# A4950_driver.net
KiCad netlist of a schematic drawn in Altium Designer
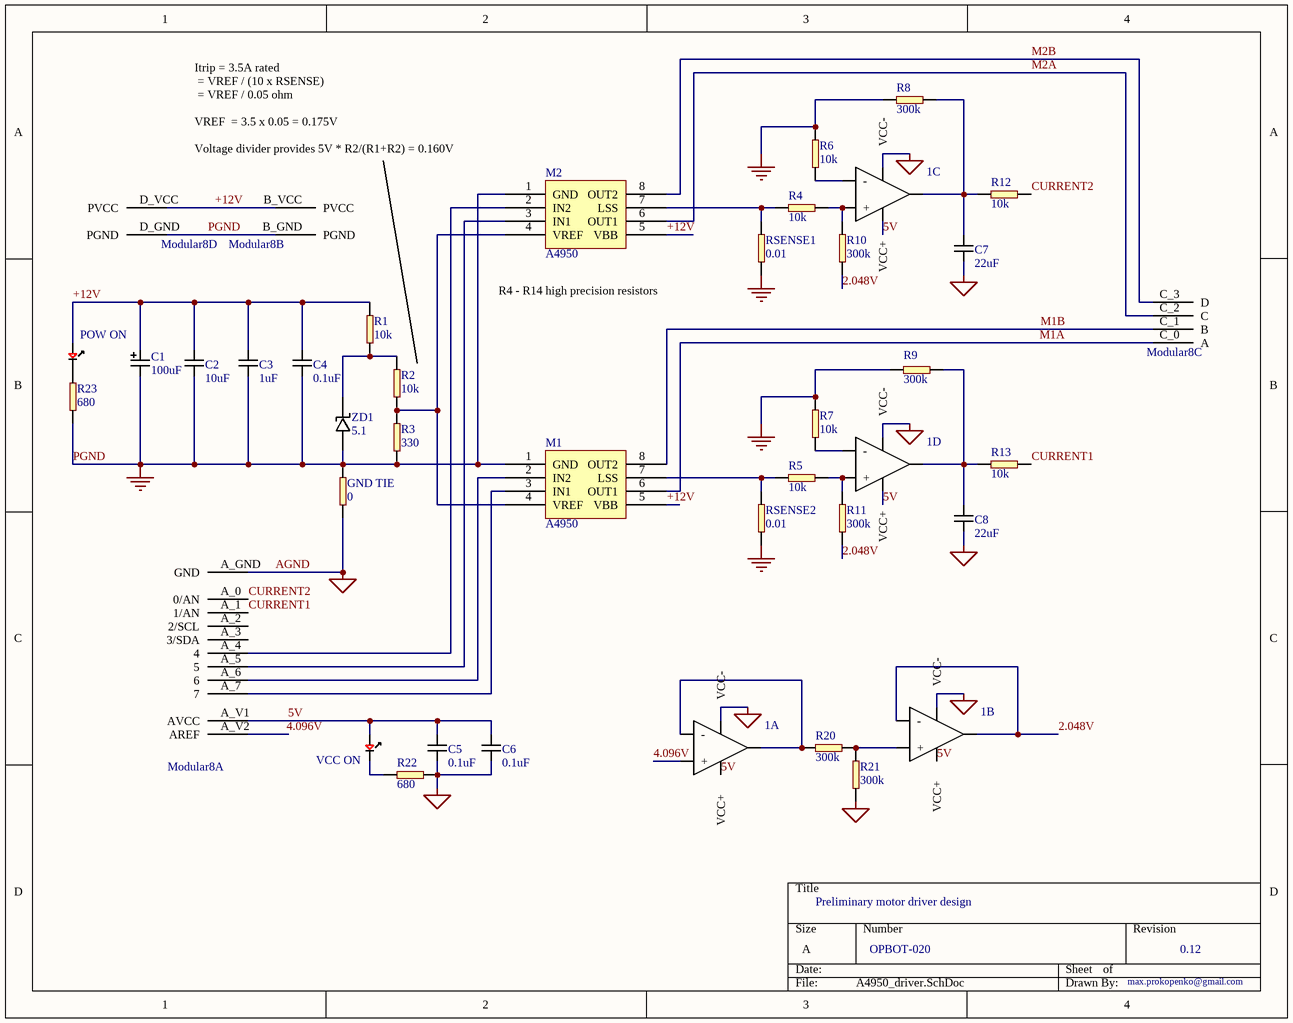
[diagram p0: A4950_driver.SchDoc]

(export (version "E")
  (design (tool "Eeschema 10.0.6"))
  (components
    (comp (ref "1") (value "LM324DT") (footprint "SO14") (libsource (lib "OpBots") (part "LM324DT")))
    (comp (ref "C1")
      (value "C 100uF 25V")
      (footprint "RADIAL CAP 6.5mm")
      (fields (field (name "C") "100uF"))
      (libsource (lib "RLC") (part "C 100uF 25V"))
    )
    (comp (ref "C2")
      (value "C 10uF 25V")
      (footprint "0603")
      (fields (field (name "C") "10uF"))
      (libsource (lib "RLC") (part "C 10uF 25V"))
    )
    (comp (ref "C3")
      (value "C 1uF 25V")
      (footprint "0603")
      (fields (field (name "C") "1uF"))
      (libsource (lib "RLC") (part "C 1uF 25V"))
    )
    (comp (ref "C4")
      (value "C 0.1uF 25V")
      (footprint "0603")
      (fields (field (name "C") "0.1uF"))
      (libsource (lib "RLC") (part "C 0.1uF 25V"))
    )
    (comp (ref "C5")
      (value "C 0.1uF 25V")
      (footprint "0603")
      (fields (field (name "C") "0.1uF"))
      (libsource (lib "RLC") (part "C 0.1uF 25V"))
    )
    (comp (ref "C6")
      (value "C 0.1uF 25V")
      (footprint "0603")
      (fields (field (name "C") "0.1uF"))
      (libsource (lib "RLC") (part "C 0.1uF 25V"))
    )
    (comp (ref "C7")
      (value "C 22uF 6.3V")
      (footprint "0603")
      (fields (field (name "C") "22uF"))
      (libsource (lib "RLC") (part "C 22uF 6.3V"))
    )
    (comp (ref "C8")
      (value "C 22uF 6.3V")
      (footprint "0603")
      (fields (field (name "C") "22uF"))
      (libsource (lib "RLC") (part "C 22uF 6.3V"))
    )
    (comp (ref "GND TIE")
      (value "R 0")
      (footprint "0603")
      (fields (field (name "R") "0"))
      (libsource (lib "RLC") (part "R 0"))
    )
    (comp (ref "M1")
      (value "A4950")
      (footprint "SOICN8 thermal pad")
      (libsource (lib "OpBots") (part "A4950"))
    )
    (comp (ref "M2")
      (value "A4950")
      (footprint "SOICN8 thermal pad")
      (libsource (lib "OpBots") (part "A4950"))
    )
    (comp (ref "Modular8")
      (value "modular8_power")
      (footprint "modular8 metric power")
      (libsource (lib "OpBots") (part "modular8_power"))
    )
    (comp (ref "POW ON") (value "LEDG") (footprint "0805 - LED") (libsource (lib "OpBots") (part "LEDG")))
    (comp (ref "R1")
      (value "R 10k")
      (footprint "0603")
      (fields (field (name "R") "10k"))
      (libsource (lib "RLC") (part "R 10k"))
    )
    (comp (ref "R2")
      (value "R 10k")
      (footprint "0603")
      (fields (field (name "R") "10k"))
      (libsource (lib "RLC") (part "R 10k"))
    )
    (comp (ref "R3")
      (value "R 330")
      (footprint "0603")
      (fields (field (name "R") "330"))
      (libsource (lib "RLC") (part "R 330"))
    )
    (comp (ref "R4")
      (value "R 10k 1%")
      (footprint "0603")
      (fields (field (name "R") "10k"))
      (libsource (lib "") (part "R 10k 1%_1"))
    )
    (comp (ref "R5")
      (value "R 10k 1%")
      (footprint "0603")
      (fields (field (name "R") "10k"))
      (libsource (lib "") (part "R 10k 1%_1"))
    )
    (comp (ref "R6")
      (value "R 10k 1%")
      (footprint "0603")
      (fields (field (name "R") "10k"))
      (libsource (lib "RLC") (part "R 10k 1%"))
    )
    (comp (ref "R7")
      (value "R 10k 1%")
      (footprint "0603")
      (fields (field (name "R") "10k"))
      (libsource (lib "RLC") (part "R 10k 1%"))
    )
    (comp (ref "R8")
      (value "R 300k 1%")
      (footprint "0603")
      (fields (field (name "R") "300k"))
      (libsource (lib "") (part "R 300k 1%_2"))
    )
    (comp (ref "R9")
      (value "R 300k 1%")
      (footprint "0603")
      (fields (field (name "R") "300k"))
      (libsource (lib "") (part "R 300k 1%_2"))
    )
    (comp (ref "R10")
      (value "R 300k 1%")
      (footprint "0603")
      (fields (field (name "R") "300k"))
      (libsource (lib "") (part "R 300k 1%_1"))
    )
    (comp (ref "R11")
      (value "R 300k 1%")
      (footprint "0603")
      (fields (field (name "R") "300k"))
      (libsource (lib "") (part "R 300k 1%_1"))
    )
    (comp (ref "R12")
      (value "R 10k")
      (footprint "0603")
      (fields (field (name "R") "10k"))
      (libsource (lib "") (part "R 10k_1"))
    )
    (comp (ref "R13")
      (value "R 10k")
      (footprint "0603")
      (fields (field (name "R") "10k"))
      (libsource (lib "") (part "R 10k_1"))
    )
    (comp (ref "R20")
      (value "R 300k 1%")
      (footprint "0603")
      (fields (field (name "R") "300k"))
      (libsource (lib "RLC") (part "R 300k 1%"))
    )
    (comp (ref "R21")
      (value "R 300k 1%")
      (footprint "0603")
      (fields (field (name "R") "300k"))
      (libsource (lib "") (part "R 300k 1%_1"))
    )
    (comp (ref "R22")
      (value "R 680")
      (footprint "0603")
      (fields (field (name "R") "680"))
      (libsource (lib "RLC") (part "R 680"))
    )
    (comp (ref "R23")
      (value "R 680")
      (footprint "0603")
      (fields (field (name "R") "680"))
      (libsource (lib "") (part "R 680_1"))
    )
    (comp (ref "RSENSE1")
      (value "R 0.01 0.5%")
      (footprint "1206 SPLIT")
      (fields (field (name "R") "0.01"))
      (libsource (lib "RLC") (part "R 0.01 0.5%"))
    )
    (comp (ref "RSENSE2")
      (value "R 0.01 0.5%")
      (footprint "1206 SPLIT")
      (fields (field (name "R") "0.01"))
      (libsource (lib "RLC") (part "R 0.01 0.5%"))
    )
    (comp (ref "VCC ON") (value "LEDG") (footprint "0805 - LED") (libsource (lib "OpBots") (part "LEDG")))
    (comp (ref "ZD1")
      (value "Zener 5.1V")
      (footprint "SOD-323F")
      (fields (field (name "VOLTAGE") "5.1"))
      (libsource (lib "OpBots") (part "Zener 5.1V"))
    )
  )
  (nets
    (net (code "1") (name "/+12V") (class "Default")
      (node (ref "C1") (pin "1") (pintype "passive"))
      (node (ref "C2") (pin "1") (pintype "passive"))
      (node (ref "C3") (pin "1") (pintype "passive"))
      (node (ref "C4") (pin "1") (pintype "passive"))
      (node (ref "M1") (pin "5") (pinfunction "VBB_5") (pintype "passive"))
      (node (ref "M2") (pin "5") (pinfunction "VBB_5") (pintype "passive"))
      (node (ref "Modular8") (pin "B_VCC") (pinfunction "PVCC_B_VCC") (pintype "passive"))
      (node (ref "Modular8") (pin "D_VCC") (pinfunction "PVCC_D_VCC") (pintype "passive"))
      (node (ref "POW ON") (pin "1") (pinfunction "A_1") (pintype "passive"))
      (node (ref "R1") (pin "1") (pintype "passive"))
    )
    (net (code "2") (name "/2.048V") (class "Default")
      (node (ref "1") (pin "6") (pinfunction "-_6") (pintype "passive"))
      (node (ref "1") (pin "7") (pinfunction "OUT_7") (pintype "passive"))
      (node (ref "R10") (pin "2") (pintype "passive"))
      (node (ref "R11") (pin "2") (pintype "passive"))
    )
    (net (code "3") (name "/4.096V") (class "Default")
      (node (ref "1") (pin "3") (pinfunction "+_3") (pintype "passive"))
      (node (ref "Modular8") (pin "A_V2") (pinfunction "AREF_A_V2") (pintype "passive"))
    )
    (net (code "4") (name "/5V") (class "Default")
      (node (ref "1") (pin "4") (pinfunction "VCC+_4") (pintype "passive"))
      (node (ref "C5") (pin "1") (pintype "passive"))
      (node (ref "C6") (pin "1") (pintype "passive"))
      (node (ref "Modular8") (pin "A_V1") (pinfunction "AVCC_A_V1") (pintype "passive"))
      (node (ref "VCC ON") (pin "1") (pinfunction "A_1") (pintype "passive"))
    )
    (net (code "5") (name "/CURRENT1") (class "Default")
      (node (ref "Modular8") (pin "A_1") (pinfunction "1/AN_A_1") (pintype "passive"))
      (node (ref "R13") (pin "2") (pintype "passive"))
    )
    (net (code "6") (name "/CURRENT2") (class "Default")
      (node (ref "Modular8") (pin "A_0") (pinfunction "0/AN_A_0") (pintype "passive"))
      (node (ref "R12") (pin "2") (pintype "passive"))
    )
    (net (code "7") (name "/M1A") (class "Default")
      (node (ref "M1") (pin "6") (pinfunction "OUT1_6") (pintype "passive"))
      (node (ref "Modular8") (pin "C_0") (pinfunction "A_C_0") (pintype "passive"))
    )
    (net (code "8") (name "/M1B") (class "Default")
      (node (ref "M1") (pin "8") (pinfunction "OUT2_8") (pintype "passive"))
      (node (ref "Modular8") (pin "C_1") (pinfunction "B_C_1") (pintype "passive"))
    )
    (net (code "9") (name "/M2A") (class "Default")
      (node (ref "M2") (pin "6") (pinfunction "OUT1_6") (pintype "passive"))
      (node (ref "Modular8") (pin "C_2") (pinfunction "C_C_2") (pintype "passive"))
    )
    (net (code "10") (name "/M2B") (class "Default")
      (node (ref "M2") (pin "8") (pinfunction "OUT2_8") (pintype "passive"))
      (node (ref "Modular8") (pin "C_3") (pinfunction "D_C_3") (pintype "passive"))
    )
    (net (code "11") (name "AGND") (class "Default")
      (node (ref "1") (pin "11") (pinfunction "VCC-_11") (pintype "passive"))
      (node (ref "C5") (pin "2") (pintype "passive"))
      (node (ref "C6") (pin "2") (pintype "passive"))
      (node (ref "C7") (pin "2") (pintype "passive"))
      (node (ref "C8") (pin "2") (pintype "passive"))
      (node (ref "GND TIE") (pin "2") (pintype "passive"))
      (node (ref "Modular8") (pin "A_GND") (pinfunction "GND_A_GND") (pintype "passive"))
      (node (ref "R21") (pin "2") (pintype "passive"))
      (node (ref "R22") (pin "2") (pintype "passive"))
    )
    (net (code "12") (name "Net-(1A--)") (class "Default")
      (node (ref "1") (pin "1") (pinfunction "OUT_1") (pintype "passive"))
      (node (ref "1") (pin "2") (pinfunction "-_2") (pintype "passive"))
      (node (ref "R20") (pin "2") (pintype "passive"))
    )
    (net (code "13") (name "Net-(1B-+)") (class "Default")
      (node (ref "1") (pin "5") (pinfunction "+_5") (pintype "passive"))
      (node (ref "R20") (pin "1") (pintype "passive"))
      (node (ref "R21") (pin "1") (pintype "passive"))
    )
    (net (code "14") (name "Net-(1C-+)") (class "Default")
      (node (ref "1") (pin "10") (pinfunction "+_10") (pintype "passive"))
      (node (ref "R10") (pin "1") (pintype "passive"))
      (node (ref "R4") (pin "2") (pintype "passive"))
    )
    (net (code "15") (name "Net-(1C--)") (class "Default")
      (node (ref "1") (pin "9") (pinfunction "-_9") (pintype "passive"))
      (node (ref "R6") (pin "1") (pintype "passive"))
    )
    (net (code "16") (name "Net-(1C-OUT)") (class "Default")
      (node (ref "1") (pin "8") (pinfunction "OUT_8") (pintype "passive"))
      (node (ref "C7") (pin "1") (pintype "passive"))
      (node (ref "R12") (pin "1") (pintype "passive"))
      (node (ref "R8") (pin "2") (pintype "passive"))
    )
    (net (code "17") (name "Net-(1D-+)") (class "Default")
      (node (ref "1") (pin "12") (pinfunction "+_12") (pintype "passive"))
      (node (ref "R11") (pin "1") (pintype "passive"))
      (node (ref "R5") (pin "2") (pintype "passive"))
    )
    (net (code "18") (name "Net-(1D--)") (class "Default")
      (node (ref "1") (pin "13") (pinfunction "-_13") (pintype "passive"))
      (node (ref "R7") (pin "1") (pintype "passive"))
    )
    (net (code "19") (name "Net-(1D-OUT)") (class "Default")
      (node (ref "1") (pin "14") (pinfunction "OUT_14") (pintype "passive"))
      (node (ref "C8") (pin "1") (pintype "passive"))
      (node (ref "R13") (pin "1") (pintype "passive"))
      (node (ref "R9") (pin "2") (pintype "passive"))
    )
    (net (code "20") (name "Net-(M1-IN1)") (class "Default")
      (node (ref "M1") (pin "3") (pinfunction "IN1_3") (pintype "passive"))
      (node (ref "Modular8") (pin "A_7") (pinfunction "7_A_7") (pintype "passive"))
    )
    (net (code "21") (name "Net-(M1-IN2)") (class "Default")
      (node (ref "M1") (pin "2") (pinfunction "IN2_2") (pintype "passive"))
      (node (ref "Modular8") (pin "A_6") (pinfunction "6_A_6") (pintype "passive"))
    )
    (net (code "22") (name "Net-(M1-LSS)") (class "Default")
      (node (ref "M1") (pin "7") (pinfunction "LSS_7") (pintype "passive"))
      (node (ref "R5") (pin "1") (pintype "passive"))
      (node (ref "RSENSE2") (pin "1") (pintype "passive"))
    )
    (net (code "23") (name "Net-(M1-VREF)") (class "Default")
      (node (ref "M1") (pin "4") (pinfunction "VREF_4") (pintype "passive"))
      (node (ref "M2") (pin "4") (pinfunction "VREF_4") (pintype "passive"))
      (node (ref "R2") (pin "2") (pintype "passive"))
      (node (ref "R3") (pin "1") (pintype "passive"))
    )
    (net (code "24") (name "Net-(M2-IN1)") (class "Default")
      (node (ref "M2") (pin "3") (pinfunction "IN1_3") (pintype "passive"))
      (node (ref "Modular8") (pin "A_5") (pinfunction "5_A_5") (pintype "passive"))
    )
    (net (code "25") (name "Net-(M2-IN2)") (class "Default")
      (node (ref "M2") (pin "2") (pinfunction "IN2_2") (pintype "passive"))
      (node (ref "Modular8") (pin "A_4") (pinfunction "4_A_4") (pintype "passive"))
    )
    (net (code "26") (name "Net-(M2-LSS)") (class "Default")
      (node (ref "M2") (pin "7") (pinfunction "LSS_7") (pintype "passive"))
      (node (ref "R4") (pin "1") (pintype "passive"))
      (node (ref "RSENSE1") (pin "1") (pintype "passive"))
    )
    (net (code "27") (name "Net-(POW ON-K)") (class "Default")
      (node (ref "POW ON") (pin "2") (pinfunction "K_2") (pintype "passive"))
      (node (ref "R23") (pin "1") (pintype "passive"))
    )
    (net (code "28") (name "Net-(R1-Pad2)") (class "Default")
      (node (ref "R1") (pin "2") (pintype "passive"))
      (node (ref "R2") (pin "1") (pintype "passive"))
      (node (ref "ZD1") (pin "1") (pinfunction "1_1") (pintype "passive"))
    )
    (net (code "29") (name "Net-(VCC ON-K)") (class "Default")
      (node (ref "R22") (pin "1") (pintype "passive"))
      (node (ref "VCC ON") (pin "2") (pinfunction "K_2") (pintype "passive"))
    )
    (net (code "30") (name "PGND") (class "Default")
      (node (ref "C1") (pin "2") (pintype "passive"))
      (node (ref "C2") (pin "2") (pintype "passive"))
      (node (ref "C3") (pin "2") (pintype "passive"))
      (node (ref "C4") (pin "2") (pintype "passive"))
      (node (ref "GND TIE") (pin "1") (pintype "passive"))
      (node (ref "M1") (pin "1") (pinfunction "GND_1") (pintype "passive"))
      (node (ref "M2") (pin "1") (pinfunction "GND_1") (pintype "passive"))
      (node (ref "Modular8") (pin "B_GND") (pinfunction "PGND_B_GND") (pintype "passive"))
      (node (ref "Modular8") (pin "D_GND") (pinfunction "PGND_D_GND") (pintype "passive"))
      (node (ref "R23") (pin "2") (pintype "passive"))
      (node (ref "R3") (pin "2") (pintype "passive"))
      (node (ref "R6") (pin "2") (pintype "passive"))
      (node (ref "R7") (pin "2") (pintype "passive"))
      (node (ref "R8") (pin "1") (pintype "passive"))
      (node (ref "R9") (pin "1") (pintype "passive"))
      (node (ref "RSENSE1") (pin "2") (pintype "passive"))
      (node (ref "RSENSE2") (pin "2") (pintype "passive"))
      (node (ref "ZD1") (pin "2") (pinfunction "2_2") (pintype "passive"))
    )
    (net (code "31") (name "unconnected-(Modular8A-2{slash}SCL-PadA_2)") (class "Default")
      (node (ref "Modular8") (pin "A_2") (pinfunction "2/SCL_A_2") (pintype "passive"))
    )
    (net (code "32") (name "unconnected-(Modular8A-3{slash}SDA-PadA_3)") (class "Default")
      (node (ref "Modular8") (pin "A_3") (pinfunction "3/SDA_A_3") (pintype "passive"))
    )
  )
)
